# main_ver2.net
KiCad netlist of a schematic drawn in EAGLE
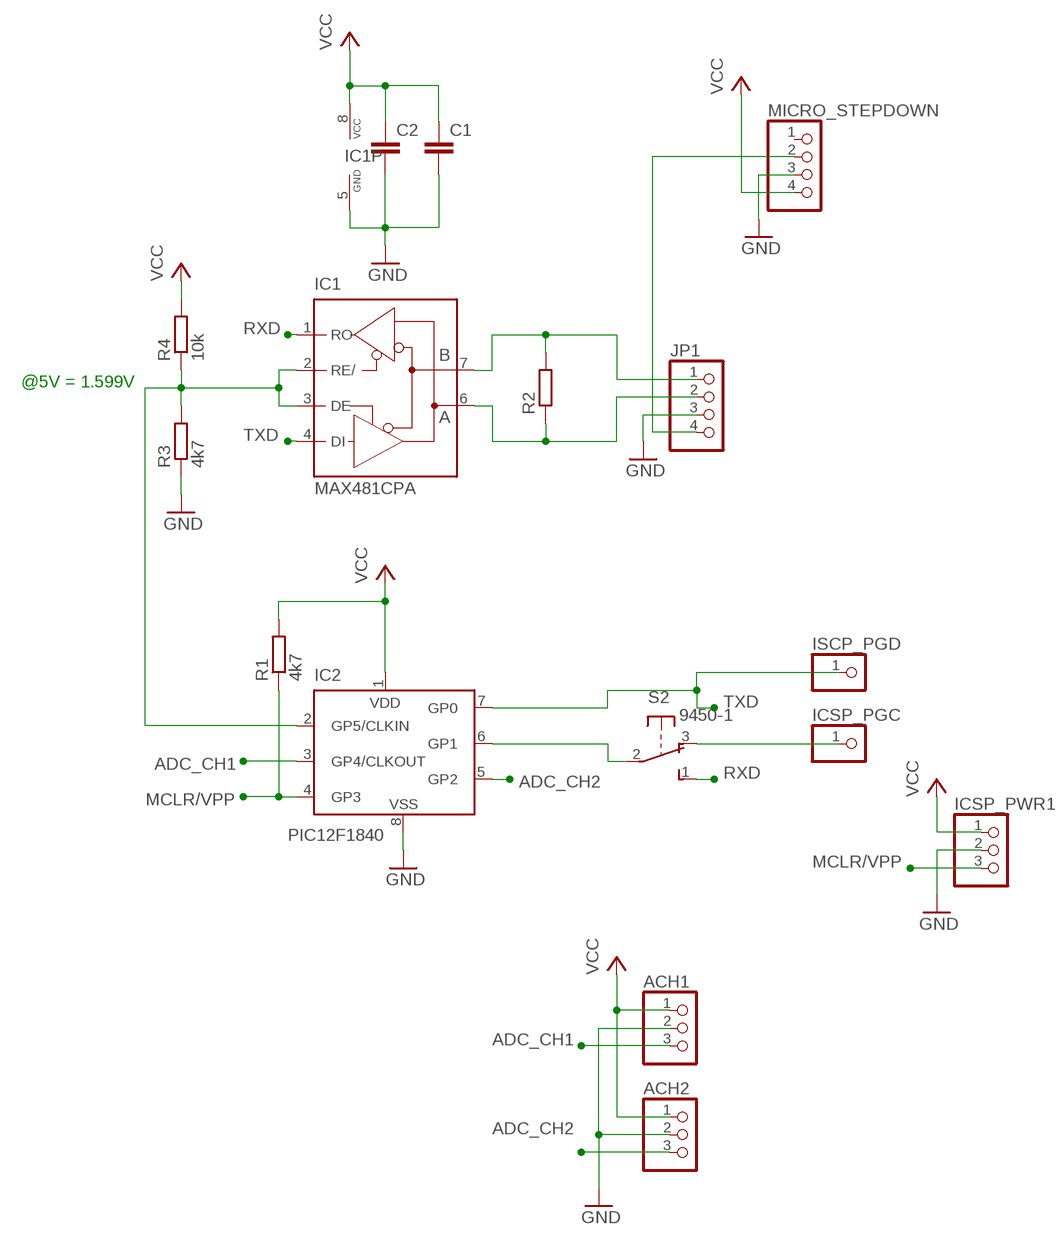
[diagram p0: schematic, sheet 1]

(export (version "E")
  (design (tool "Eeschema 10.0.6"))
  (components
    (comp (ref "ACH1")
      (value "PINHD-1X3")
      (footprint "eagle-import:1X03")
      (libsource (lib "eagle-import") (part "PINHD-1X3"))
    )
    (comp (ref "ACH2")
      (value "PINHD-1X3")
      (footprint "eagle-import:1X03")
      (libsource (lib "eagle-import") (part "PINHD-1X3"))
    )
    (comp (ref "C1")
      (value "C-EUC0603")
      (footprint "eagle-import:C0603")
      (libsource (lib "eagle-import") (part "C-EUC0603"))
    )
    (comp (ref "C2")
      (value "C-EUC0603")
      (footprint "eagle-import:C0603")
      (libsource (lib "eagle-import") (part "C-EUC0603"))
    )
    (comp (ref "IC1")
      (value "MAX481CPA")
      (footprint "eagle-import:DIL08")
      (fields (field (name "MPN") "MAX481CPA+"))
      (libsource (lib "eagle-import") (part "MAX481CPA"))
    )
    (comp (ref "IC2")
      (value "PIC12F1840")
      (footprint "eagle-import:DIL8")
      (fields (field (name "MF") "MICROCHIP") (field (name "MPN") "PIC12F629-I/P"))
      (libsource (lib "eagle-import") (part "PIC12F6P29"))
    )
    (comp (ref "ICSP_PGC")
      (value "PINHD-1X1")
      (footprint "eagle-import:1X01")
      (libsource (lib "eagle-import") (part "PINHD-1X1"))
    )
    (comp (ref "ICSP_PWR1")
      (value "PINHD-1X3")
      (footprint "eagle-import:1X03")
      (libsource (lib "eagle-import") (part "PINHD-1X3"))
    )
    (comp (ref "ISCP_PGD")
      (value "PINHD-1X1")
      (footprint "eagle-import:1X01")
      (libsource (lib "eagle-import") (part "PINHD-1X1"))
    )
    (comp (ref "JP1")
      (value "PINHD-1X4")
      (footprint "eagle-import:1X04")
      (libsource (lib "eagle-import") (part "PINHD-1X4"))
    )
    (comp (ref "MICRO_STEPDOWN")
      (value "PINHD-1X4/90")
      (footprint "eagle-import:1X04_90")
      (libsource (lib "eagle-import") (part "PINHD-1X4/90"))
    )
    (comp (ref "R1")
      (value "4k7")
      (footprint "eagle-import:R0603")
      (libsource (lib "eagle-import") (part "R-EU_R0603"))
    )
    (comp (ref "R2")
      (value "R-EU_R0603")
      (footprint "eagle-import:R0603")
      (libsource (lib "eagle-import") (part "R-EU_R0603"))
    )
    (comp (ref "R3")
      (value "4k7")
      (footprint "eagle-import:R0603")
      (libsource (lib "eagle-import") (part "R-EU_R0603"))
    )
    (comp (ref "R4")
      (value "10k")
      (footprint "eagle-import:R0603")
      (libsource (lib "eagle-import") (part "R-EU_R0603"))
    )
    (comp (ref "S2")
      (value "9450-1")
      (footprint "eagle-import:9450-1")
      (libsource (lib "eagle-import") (part "9450-1"))
    )
  )
  (nets
    (net (code "1") (name "/ADC_CH1") (class "Default")
      (node (ref "ACH1") (pin "3") (pinfunction "3_3") (pintype "passive"))
      (node (ref "IC2") (pin "3") (pinfunction "GP4/CLKOUT_3") (pintype "bidirectional"))
    )
    (net (code "2") (name "/ADC_CH2") (class "Default")
      (node (ref "ACH2") (pin "3") (pinfunction "3_3") (pintype "passive"))
      (node (ref "IC2") (pin "5") (pinfunction "GP2_5") (pintype "bidirectional"))
    )
    (net (code "3") (name "/MCLR{slash}VPP") (class "Default")
      (node (ref "IC2") (pin "4") (pinfunction "GP3_4") (pintype "input"))
      (node (ref "ICSP_PWR1") (pin "3") (pinfunction "3_3") (pintype "passive"))
      (node (ref "R1") (pin "1") (pinfunction "1_1") (pintype "passive"))
    )
    (net (code "4") (name "/RXD") (class "Default")
      (node (ref "IC1") (pin "1") (pinfunction "RO_1") (pintype "output"))
      (node (ref "S2") (pin "1") (pinfunction "S_1") (pintype "passive"))
    )
    (net (code "5") (name "/TXD") (class "Default")
      (node (ref "IC1") (pin "4") (pinfunction "DI_4") (pintype "input"))
      (node (ref "IC2") (pin "7") (pinfunction "GP0_7") (pintype "bidirectional"))
      (node (ref "ISCP_PGD") (pin "1") (pinfunction "1_1") (pintype "passive"))
    )
    (net (code "6") (name "GND") (class "Default")
      (node (ref "ACH1") (pin "2") (pinfunction "2_2") (pintype "passive"))
      (node (ref "ACH2") (pin "2") (pinfunction "2_2") (pintype "passive"))
      (node (ref "C1") (pin "2") (pinfunction "2_2") (pintype "passive"))
      (node (ref "C2") (pin "2") (pinfunction "2_2") (pintype "passive"))
      (node (ref "IC1") (pin "5") (pinfunction "GND_5") (pintype "power_in"))
      (node (ref "IC2") (pin "8") (pinfunction "VSS_8") (pintype "power_in"))
      (node (ref "ICSP_PWR1") (pin "2") (pinfunction "2_2") (pintype "passive"))
      (node (ref "JP1") (pin "3") (pinfunction "3_3") (pintype "passive"))
      (node (ref "MICRO_STEPDOWN") (pin "3") (pinfunction "3_3") (pintype "passive"))
      (node (ref "R3") (pin "1") (pinfunction "1_1") (pintype "passive"))
    )
    (net (code "7") (name "Net-(IC1A-A)") (class "Default")
      (node (ref "IC1") (pin "6") (pinfunction "A_6") (pintype "passive"))
      (node (ref "JP1") (pin "2") (pinfunction "2_2") (pintype "passive"))
      (node (ref "R2") (pin "1") (pinfunction "1_1") (pintype "passive"))
    )
    (net (code "8") (name "Net-(IC1A-B)") (class "Default")
      (node (ref "IC1") (pin "7") (pinfunction "B_7") (pintype "passive"))
      (node (ref "JP1") (pin "1") (pinfunction "1_1") (pintype "passive"))
      (node (ref "R2") (pin "2") (pinfunction "2_2") (pintype "passive"))
    )
    (net (code "9") (name "Net-(IC1A-DE)") (class "Default")
      (node (ref "IC1") (pin "2") (pinfunction "RE/_2") (pintype "input"))
      (node (ref "IC1") (pin "3") (pinfunction "DE_3") (pintype "input"))
      (node (ref "IC2") (pin "2") (pinfunction "GP5/CLKIN_2") (pintype "bidirectional"))
      (node (ref "R3") (pin "2") (pinfunction "2_2") (pintype "passive"))
      (node (ref "R4") (pin "1") (pinfunction "1_1") (pintype "passive"))
    )
    (net (code "10") (name "Net-(IC2-GP1)") (class "Default")
      (node (ref "IC2") (pin "6") (pinfunction "GP1_6") (pintype "bidirectional"))
      (node (ref "S2") (pin "2") (pinfunction "P_2") (pintype "passive"))
    )
    (net (code "11") (name "Net-(JP1-Pad4)") (class "Default")
      (node (ref "JP1") (pin "4") (pinfunction "4_4") (pintype "passive"))
      (node (ref "MICRO_STEPDOWN") (pin "2") (pinfunction "2_2") (pintype "passive"))
    )
    (net (code "12") (name "Net-(S2-O)") (class "Default")
      (node (ref "ICSP_PGC") (pin "1") (pinfunction "1_1") (pintype "passive"))
      (node (ref "S2") (pin "3") (pinfunction "O_3") (pintype "passive"))
    )
    (net (code "13") (name "VCC") (class "Default")
      (node (ref "ACH1") (pin "1") (pinfunction "1_1") (pintype "passive"))
      (node (ref "ACH2") (pin "1") (pinfunction "1_1") (pintype "passive"))
      (node (ref "C1") (pin "1") (pinfunction "1_1") (pintype "passive"))
      (node (ref "C2") (pin "1") (pinfunction "1_1") (pintype "passive"))
      (node (ref "IC1") (pin "8") (pinfunction "VCC_8") (pintype "power_in"))
      (node (ref "IC2") (pin "1") (pinfunction "VDD_1") (pintype "power_in"))
      (node (ref "ICSP_PWR1") (pin "1") (pinfunction "1_1") (pintype "passive"))
      (node (ref "MICRO_STEPDOWN") (pin "4") (pinfunction "4_4") (pintype "passive"))
      (node (ref "R1") (pin "2") (pinfunction "2_2") (pintype "passive"))
      (node (ref "R4") (pin "2") (pinfunction "2_2") (pintype "passive"))
    )
    (net (code "14") (name "unconnected-(MICRO_STEPDOWN-Pad1)") (class "Default")
      (node (ref "MICRO_STEPDOWN") (pin "1") (pinfunction "1_1") (pintype "passive"))
    )
  )
)
